# Microcontroller.net
KiCad netlist of a schematic drawn in Altium Designer
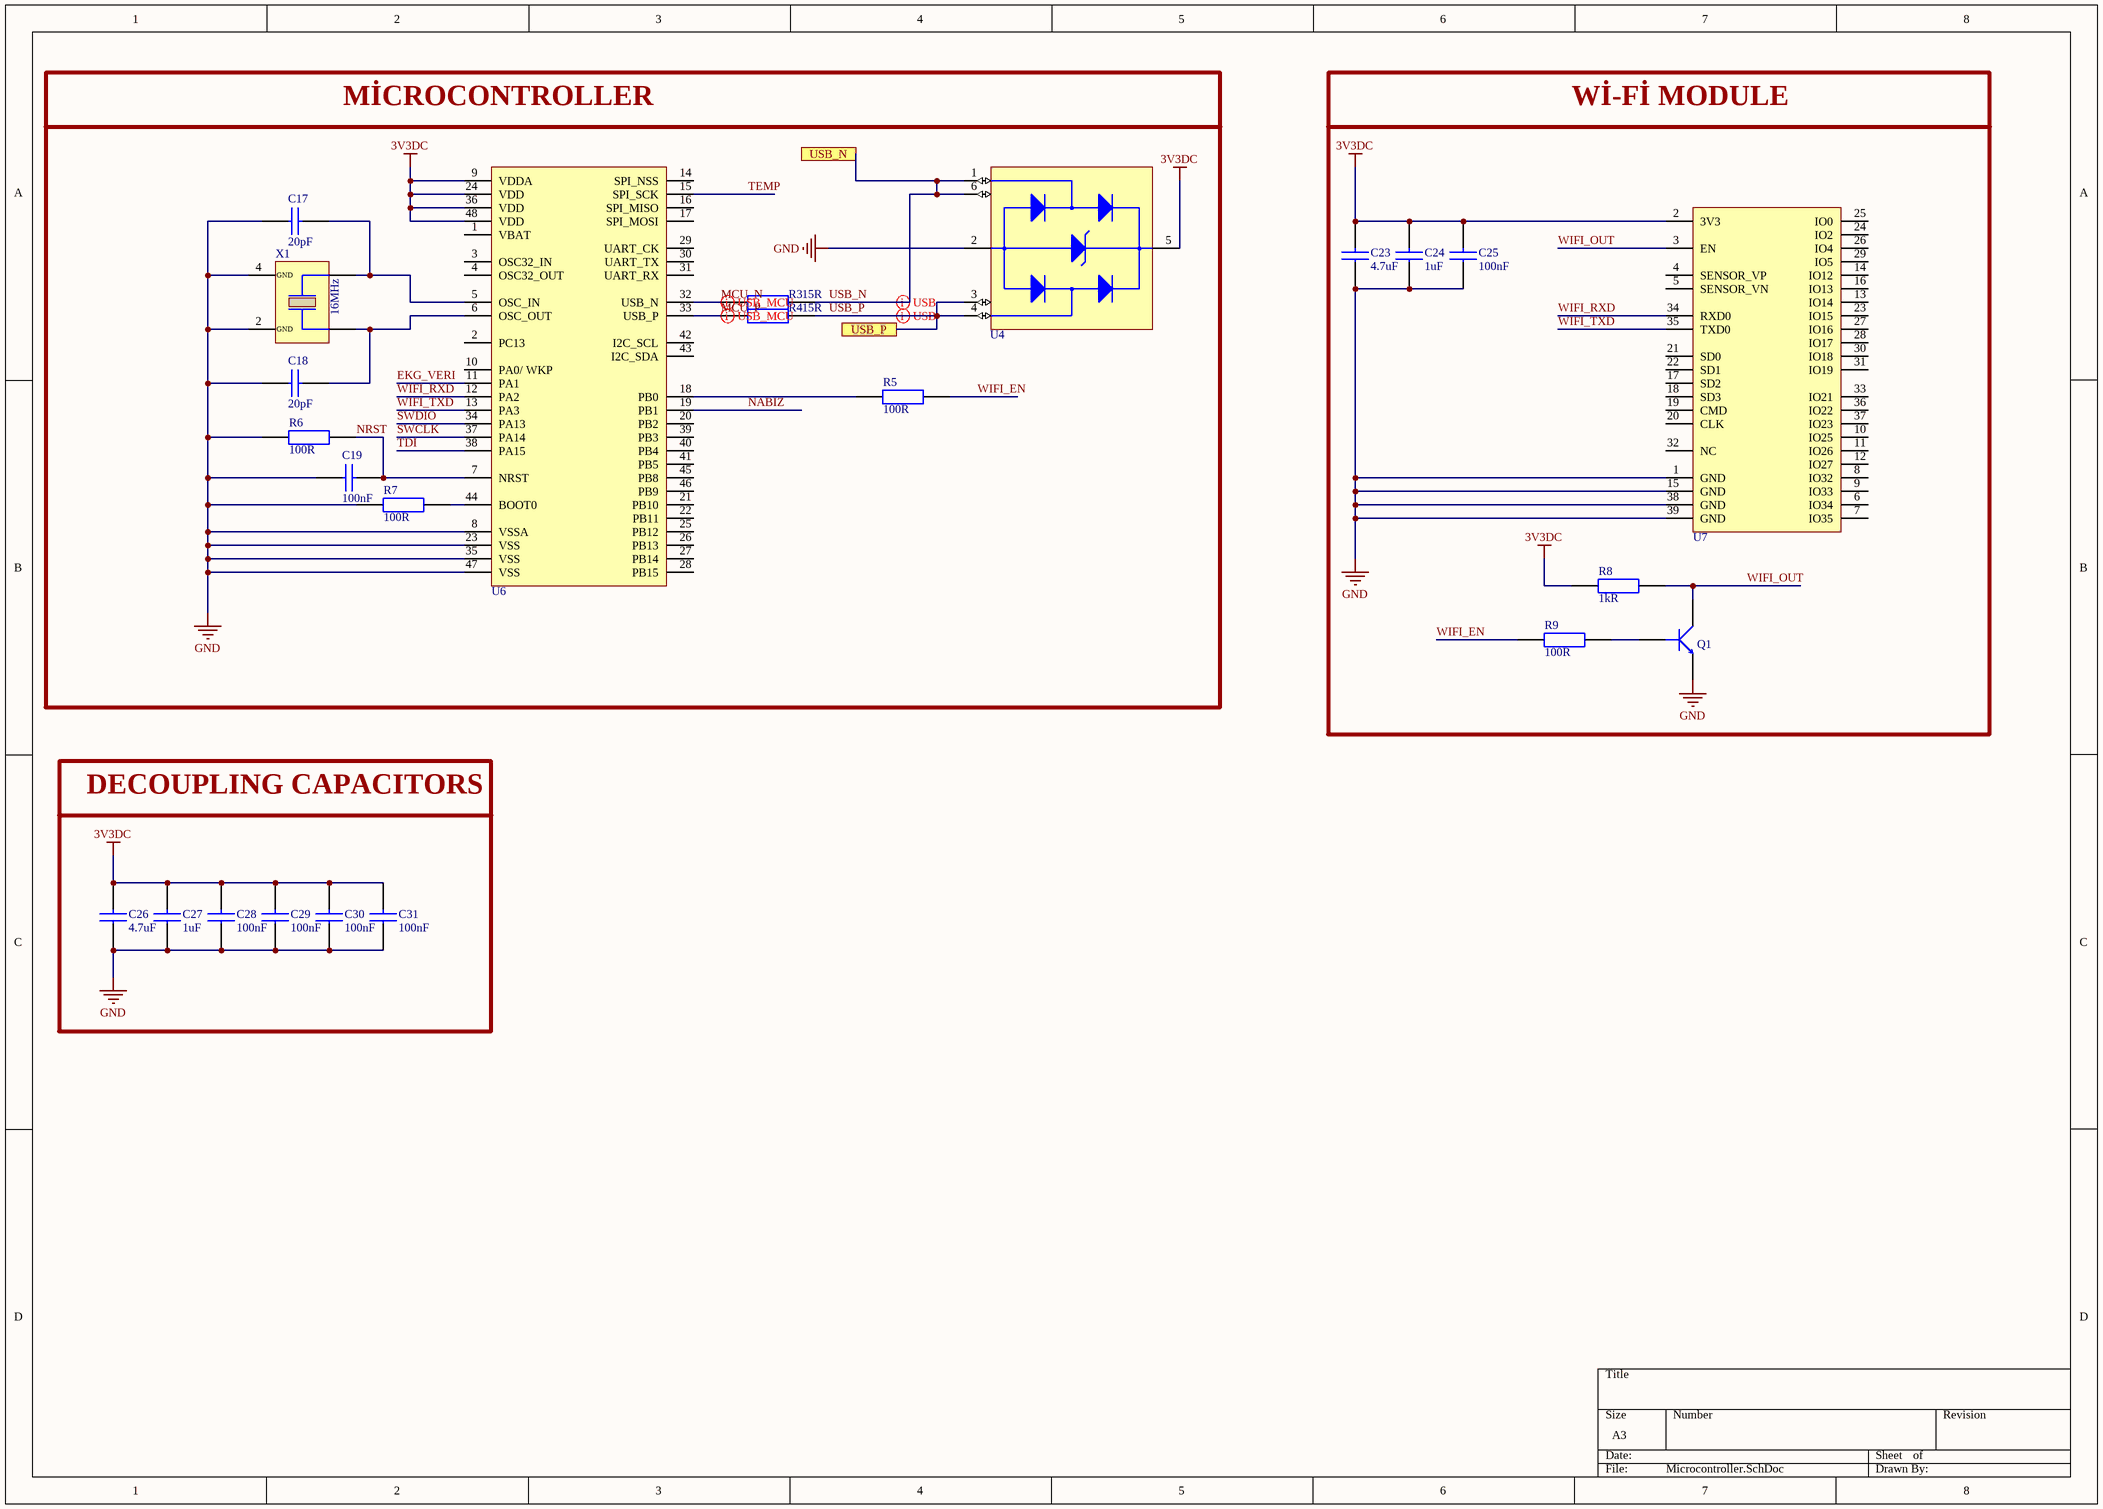
[diagram p0: Microcontroller.SchDoc]

(export (version "E")
  (design (tool "Eeschema 10.0.6"))
  (components
    (comp (ref "C17")
      (value "CL10C200JB8NNNC")
      (footprint "CAP_0603")
      (description "CAP CER 20pF %5 0603 SMD")
      (fields
        (field (name "MANUFACTURER") "Samsung")
        (field (name "TOLERANCE") "5%")
        (field (name "CAPACITANCE") "20pF")
        (field (name "DESIGNED BY") "TALAT")
      )
      (libsource (lib "Udemy_Library") (part "CAP CER 20pF 0603"))
    )
    (comp (ref "C18")
      (value "CL10C200JB8NNNC")
      (footprint "CAP_0603")
      (description "CAP CER 20pF %5 0603 SMD")
      (fields
        (field (name "MANUFACTURER") "Samsung")
        (field (name "TOLERANCE") "5%")
        (field (name "CAPACITANCE") "20pF")
        (field (name "DESIGNED BY") "TALAT")
      )
      (libsource (lib "Udemy_Library") (part "CAP CER 20pF 0603"))
    )
    (comp (ref "C19")
      (value "CL21B104KBCNNNC")
      (footprint "CAP_0805")
      (description "CAP CER 100nF %10 0805")
      (fields
        (field (name "MANUFACTURER") "Samsung")
        (field (name "TOLERANCE") "10%")
        (field (name "CAPACITANCE") "100nF")
        (field (name "DESIGNED BY") "TALAT")
      )
      (libsource (lib "Udemy_Library") (part "CAP CER 100nF 0805"))
    )
    (comp (ref "C23")
      (value "CL21A475KAQNNNE")
      (footprint "CAP_0805")
      (description "CAP CER 4.7uF %10 0805")
      (fields
        (field (name "MANUFACTURER") "Samsung")
        (field (name "TOLERANCE") "10%")
        (field (name "CAPACITANCE") "4.7uF")
        (field (name "DESIGNED BY") "TALAT")
      )
      (libsource (lib "Udemy_Library") (part "CAP CER 4.7uF 0805"))
    )
    (comp (ref "C24")
      (value "CL21B105KBFNNNE")
      (footprint "CAP_0805")
      (description "CAP CER 1uF %10 0805")
      (fields
        (field (name "MANUFACTURER") "Samsung")
        (field (name "TOLERANCE") "10%")
        (field (name "CAPACITANCE") "1uF")
        (field (name "DESIGNED BY") "TALAT")
      )
      (libsource (lib "Udemy_Library") (part "CAP CER 1uF 0805"))
    )
    (comp (ref "C25")
      (value "CL21B104KBCNNNC")
      (footprint "CAP_0805")
      (description "CAP CER 100nF %10 0805")
      (fields
        (field (name "MANUFACTURER") "Samsung")
        (field (name "TOLERANCE") "10%")
        (field (name "CAPACITANCE") "100nF")
        (field (name "DESIGNED BY") "TALAT")
      )
      (libsource (lib "Udemy_Library") (part "CAP CER 100nF 0805"))
    )
    (comp (ref "C26")
      (value "CL21A475KAQNNNE")
      (footprint "CAP_0805")
      (description "CAP CER 4.7uF %10 0805")
      (fields
        (field (name "MANUFACTURER") "Samsung")
        (field (name "TOLERANCE") "10%")
        (field (name "CAPACITANCE") "4.7uF")
        (field (name "DESIGNED BY") "TALAT")
      )
      (libsource (lib "Udemy_Library") (part "CAP CER 4.7uF 0805"))
    )
    (comp (ref "C27")
      (value "CL21B105KBFNNNE")
      (footprint "CAP_0805")
      (description "CAP CER 1uF %10 0805")
      (fields
        (field (name "MANUFACTURER") "Samsung")
        (field (name "TOLERANCE") "10%")
        (field (name "CAPACITANCE") "1uF")
        (field (name "DESIGNED BY") "TALAT")
      )
      (libsource (lib "Udemy_Library") (part "CAP CER 1uF 0805"))
    )
    (comp (ref "C28")
      (value "CL21B104KBCNNNC")
      (footprint "CAP_0805")
      (description "CAP CER 100nF %10 0805")
      (fields
        (field (name "MANUFACTURER") "Samsung")
        (field (name "TOLERANCE") "10%")
        (field (name "CAPACITANCE") "100nF")
        (field (name "DESIGNED BY") "TALAT")
      )
      (libsource (lib "Udemy_Library") (part "CAP CER 100nF 0805"))
    )
    (comp (ref "C29")
      (value "CL21B104KBCNNNC")
      (footprint "CAP_0805")
      (description "CAP CER 100nF %10 0805")
      (fields
        (field (name "MANUFACTURER") "Samsung")
        (field (name "TOLERANCE") "10%")
        (field (name "CAPACITANCE") "100nF")
        (field (name "DESIGNED BY") "TALAT")
      )
      (libsource (lib "Udemy_Library") (part "CAP CER 100nF 0805"))
    )
    (comp (ref "C30")
      (value "CL21B104KBCNNNC")
      (footprint "CAP_0805")
      (description "CAP CER 100nF %10 0805")
      (fields
        (field (name "MANUFACTURER") "Samsung")
        (field (name "TOLERANCE") "10%")
        (field (name "CAPACITANCE") "100nF")
        (field (name "DESIGNED BY") "TALAT")
      )
      (libsource (lib "Udemy_Library") (part "CAP CER 100nF 0805"))
    )
    (comp (ref "C31")
      (value "CL21B104KBCNNNC")
      (footprint "CAP_0805")
      (description "CAP CER 100nF %10 0805")
      (fields
        (field (name "MANUFACTURER") "Samsung")
        (field (name "TOLERANCE") "10%")
        (field (name "CAPACITANCE") "100nF")
        (field (name "DESIGNED BY") "TALAT")
      )
      (libsource (lib "Udemy_Library") (part "CAP CER 100nF 0805"))
    )
    (comp (ref "Q1")
      (value "MMBT3904-7-F")
      (footprint "SOT-23F")
      (description "Transistor General Purpose BJT NPN 40 Volt 0.2A Automotive 3-Pin SOT-23")
      (fields (field (name "MANUFACTURER") "Diodes Zetex") (field (name "DESIGNED BY") "TALAT"))
      (libsource (lib "Udemy_Library") (part "MMBT3904-7-F"))
    )
    (comp (ref "R3")
      (value "RC0603JR-0715RL")
      (footprint "RES_0603")
      (description "RES 15 %5 OHM 0603 SMD")
      (fields
        (field (name "MANUFACTURER") "Yageo")
        (field (name "TOLERANCE") "5%")
        (field (name "RESISTANCE") "15R")
        (field (name "DESIGNED BY") "TALAT")
      )
      (libsource (lib "Udemy_Library") (part "RES 15 OHM 0603"))
    )
    (comp (ref "R4")
      (value "RC0603JR-0715RL")
      (footprint "RES_0603")
      (description "RES 15 %5 OHM 0603 SMD")
      (fields
        (field (name "MANUFACTURER") "Yageo")
        (field (name "TOLERANCE") "5%")
        (field (name "RESISTANCE") "15R")
        (field (name "DESIGNED BY") "TALAT")
      )
      (libsource (lib "Udemy_Library") (part "RES 15 OHM 0603"))
    )
    (comp (ref "R5")
      (value "RC0603JR-07100RL")
      (footprint "RES_0603")
      (description "RES 100 %5 OHM 0603 SMD")
      (fields
        (field (name "MANUFACTURER") "Yageo")
        (field (name "TOLERANCE") "5%")
        (field (name "RESISTANCE") "100R")
        (field (name "DESIGNED BY") "TALAT")
      )
      (libsource (lib "Udemy_Library") (part "RES 100 OHM 0603"))
    )
    (comp (ref "R6")
      (value "RC0603JR-07100RL")
      (footprint "RES_0603")
      (description "RES 100 %5 OHM 0603 SMD")
      (fields
        (field (name "MANUFACTURER") "Yageo")
        (field (name "TOLERANCE") "5%")
        (field (name "RESISTANCE") "100R")
        (field (name "DESIGNED BY") "TALAT")
      )
      (libsource (lib "Udemy_Library") (part "RES 100 OHM 0603"))
    )
    (comp (ref "R7")
      (value "RC0603JR-07100RL")
      (footprint "RES_0603")
      (description "RES 100 %5 OHM 0603 SMD")
      (fields
        (field (name "MANUFACTURER") "Yageo")
        (field (name "TOLERANCE") "5%")
        (field (name "RESISTANCE") "100R")
        (field (name "DESIGNED BY") "TALAT")
      )
      (libsource (lib "Udemy_Library") (part "RES 100 OHM 0603"))
    )
    (comp (ref "R8")
      (value "RC0603FR-0710KL")
      (footprint "RES_0603")
      (description "RES 1K %1 OHM 0603 SMD")
      (fields
        (field (name "MANUFACTURER") "Yageo")
        (field (name "MANUFACTURER PART NUMBER") "RC0603JR-071KL")
        (field (name "RESISTANCE") "1kR")
        (field (name "DESIGNED BY") "TALAT")
      )
      (libsource (lib "Udemy_Library") (part "RES 1K OHM 0603"))
    )
    (comp (ref "R9")
      (value "RC0603JR-07100RL")
      (footprint "RES_0603")
      (description "RES 100 %5 OHM 0603 SMD")
      (fields
        (field (name "MANUFACTURER") "Yageo")
        (field (name "TOLERANCE") "5%")
        (field (name "RESISTANCE") "100R")
        (field (name "DESIGNED BY") "TALAT")
      )
      (libsource (lib "Udemy_Library") (part "RES 100 OHM 0603"))
    )
    (comp (ref "U4")
      (value "USBLC6-2SC6")
      (footprint "SOT23-6L")
      (description "TVS DIODE 5.25V 17V SOT23-6")
      (fields (field (name "MANUFACTURER") "STMicroelectronics") (field (name "DESIGNED BY") "TALAT"))
      (libsource (lib "Udemy_Library") (part "USB PROTECTION"))
    )
    (comp (ref "U6")
      (value "STM32F103C6T6A")
      (footprint "LQFP-48")
      (description "MCU 32-bit STM32F ARM Cortex M3 RISC 32KB Flash 2.5V/3.3V 48-Pin LQFP Tray")
      (fields (field (name "MANUFACTURER") "STMicroelectronics") (field (name "DESIGNED BY") "TALAT"))
      (libsource (lib "Udemy_Library") (part "STM32F103C6T6A"))
    )
    (comp (ref "U7")
      (value "ESP32-WROOM-32E (4MB)")
      (footprint "ESP32-32")
      (fields
        (field (name "MANUFACTURER") "Espressif Systems")
        (field (name "MANUFACTURER PART NUMBER") "ESP32-WROOM-32E(4MB)")
        (field (name "DESIGNED BY") "TALAT")
      )
      (libsource (lib "Udemy_Library") (part "ESP32-WROOM-32E (4MB)"))
    )
    (comp (ref "X1")
      (value "ECS-160-20-30B-TR")
      (footprint "ECS")
      (description "CRYSTAL 16.0000MHZ 20PF SMD")
      (fields
        (field (name "MANUFACTURER") "ECS International")
        (field (name "TOLERANCE") "50ppm")
        (field (name "FREQUENCY") "16MHz")
        (field (name "DESIGNED BY") "TALAT")
      )
      (libsource (lib "Udemy_Library") (part "CRYSTAL 16MHz"))
    )
  )
  (nets
    (net (code "1") (name "/EKG_VERI") (class "Default")
      (node (ref "U6") (pin "11") (pinfunction "PA1_11") (pintype "passive"))
    )
    (net (code "2") (name "/MCU_N") (class "Default")
      (node (ref "R3") (pin "1") (pinfunction "1_1") (pintype "passive"))
      (node (ref "U6") (pin "32") (pinfunction "USB_N_32") (pintype "passive"))
    )
    (net (code "3") (name "/MCU_P") (class "Default")
      (node (ref "R4") (pin "1") (pinfunction "1_1") (pintype "passive"))
      (node (ref "U6") (pin "33") (pinfunction "USB_P_33") (pintype "passive"))
    )
    (net (code "4") (name "/NABIZ") (class "Default")
      (node (ref "U6") (pin "19") (pinfunction "PB1_19") (pintype "passive"))
    )
    (net (code "5") (name "/NRST") (class "Default")
      (node (ref "C19") (pin "2") (pinfunction "2_2") (pintype "passive"))
      (node (ref "R6") (pin "2") (pinfunction "2_2") (pintype "passive"))
      (node (ref "U6") (pin "7") (pinfunction "NRST_7") (pintype "passive"))
    )
    (net (code "6") (name "/SWCLK") (class "Default")
      (node (ref "U6") (pin "37") (pinfunction "PA14_37") (pintype "passive"))
    )
    (net (code "7") (name "/SWDIO") (class "Default")
      (node (ref "U6") (pin "34") (pinfunction "PA13_34") (pintype "passive"))
    )
    (net (code "8") (name "/TDI") (class "Default")
      (node (ref "U6") (pin "38") (pinfunction "PA15_38") (pintype "passive"))
    )
    (net (code "9") (name "/TEMP") (class "Default")
      (node (ref "U6") (pin "15") (pinfunction "SPI_SCK_15") (pintype "passive"))
    )
    (net (code "10") (name "/USB_N") (class "Default")
      (node (ref "R3") (pin "2") (pinfunction "2_2") (pintype "passive"))
      (node (ref "U4") (pin "1") (pinfunction "I/O1_1") (pintype "bidirectional"))
      (node (ref "U4") (pin "6") (pinfunction "I/O1_6") (pintype "bidirectional"))
    )
    (net (code "11") (name "/USB_P") (class "Default")
      (node (ref "R4") (pin "2") (pinfunction "2_2") (pintype "passive"))
      (node (ref "U4") (pin "3") (pinfunction "I/O2_3") (pintype "bidirectional"))
      (node (ref "U4") (pin "4") (pinfunction "I/O2_4") (pintype "bidirectional"))
    )
    (net (code "12") (name "/WIFI_EN") (class "Default")
      (node (ref "R5") (pin "2") (pinfunction "2_2") (pintype "passive"))
      (node (ref "R9") (pin "1") (pinfunction "1_1") (pintype "passive"))
    )
    (net (code "13") (name "/WIFI_OUT") (class "Default")
      (node (ref "Q1") (pin "3") (pinfunction "C_3") (pintype "power_in"))
      (node (ref "R8") (pin "2") (pinfunction "2_2") (pintype "passive"))
      (node (ref "U7") (pin "3") (pinfunction "EN_3") (pintype "passive"))
    )
    (net (code "14") (name "/WIFI_RXD") (class "Default")
      (node (ref "U6") (pin "12") (pinfunction "PA2_12") (pintype "passive"))
      (node (ref "U7") (pin "34") (pinfunction "RXD0_34") (pintype "passive"))
    )
    (net (code "15") (name "/WIFI_TXD") (class "Default")
      (node (ref "U6") (pin "13") (pinfunction "PA3_13") (pintype "passive"))
      (node (ref "U7") (pin "35") (pinfunction "TXD0_35") (pintype "passive"))
    )
    (net (code "16") (name "3V3DC") (class "Default")
      (node (ref "C23") (pin "2") (pinfunction "2_2") (pintype "passive"))
      (node (ref "C24") (pin "2") (pinfunction "2_2") (pintype "passive"))
      (node (ref "C25") (pin "2") (pinfunction "2_2") (pintype "passive"))
      (node (ref "C26") (pin "2") (pinfunction "2_2") (pintype "passive"))
      (node (ref "C27") (pin "2") (pinfunction "2_2") (pintype "passive"))
      (node (ref "C28") (pin "2") (pinfunction "2_2") (pintype "passive"))
      (node (ref "C29") (pin "2") (pinfunction "2_2") (pintype "passive"))
      (node (ref "C30") (pin "2") (pinfunction "2_2") (pintype "passive"))
      (node (ref "C31") (pin "2") (pinfunction "2_2") (pintype "passive"))
      (node (ref "R8") (pin "1") (pinfunction "1_1") (pintype "passive"))
      (node (ref "U4") (pin "5") (pinfunction "VBUS_5") (pintype "power_in"))
      (node (ref "U6") (pin "24") (pinfunction "VDD_24") (pintype "passive"))
      (node (ref "U6") (pin "36") (pinfunction "VDD_36") (pintype "passive"))
      (node (ref "U6") (pin "48") (pinfunction "VDD_48") (pintype "passive"))
      (node (ref "U6") (pin "9") (pinfunction "VDDA_9") (pintype "passive"))
      (node (ref "U7") (pin "2") (pinfunction "3V3_2") (pintype "passive"))
    )
    (net (code "17") (name "GND") (class "Default")
      (node (ref "C17") (pin "1") (pinfunction "1_1") (pintype "passive"))
      (node (ref "C18") (pin "1") (pinfunction "1_1") (pintype "passive"))
      (node (ref "C19") (pin "1") (pinfunction "1_1") (pintype "passive"))
      (node (ref "C23") (pin "1") (pinfunction "1_1") (pintype "passive"))
      (node (ref "C24") (pin "1") (pinfunction "1_1") (pintype "passive"))
      (node (ref "C25") (pin "1") (pinfunction "1_1") (pintype "passive"))
      (node (ref "C26") (pin "1") (pinfunction "1_1") (pintype "passive"))
      (node (ref "C27") (pin "1") (pinfunction "1_1") (pintype "passive"))
      (node (ref "C28") (pin "1") (pinfunction "1_1") (pintype "passive"))
      (node (ref "C29") (pin "1") (pinfunction "1_1") (pintype "passive"))
      (node (ref "C30") (pin "1") (pinfunction "1_1") (pintype "passive"))
      (node (ref "C31") (pin "1") (pinfunction "1_1") (pintype "passive"))
      (node (ref "Q1") (pin "2") (pinfunction "E_2") (pintype "power_in"))
      (node (ref "R6") (pin "1") (pinfunction "1_1") (pintype "passive"))
      (node (ref "R7") (pin "1") (pinfunction "1_1") (pintype "passive"))
      (node (ref "U4") (pin "2") (pinfunction "GND_2") (pintype "power_in"))
      (node (ref "U6") (pin "23") (pinfunction "VSS_23") (pintype "passive"))
      (node (ref "U6") (pin "35") (pinfunction "VSS_35") (pintype "passive"))
      (node (ref "U6") (pin "47") (pinfunction "VSS_47") (pintype "passive"))
      (node (ref "U6") (pin "8") (pinfunction "VSSA_8") (pintype "passive"))
      (node (ref "U7") (pin "1") (pinfunction "GND_1") (pintype "passive"))
      (node (ref "U7") (pin "15") (pinfunction "GND_15") (pintype "passive"))
      (node (ref "U7") (pin "38") (pinfunction "GND_38") (pintype "passive"))
      (node (ref "U7") (pin "39") (pinfunction "GND_39") (pintype "passive"))
      (node (ref "X1") (pin "2") (pinfunction "GND_2") (pintype "passive"))
      (node (ref "X1") (pin "4") (pinfunction "GND_4") (pintype "passive"))
    )
    (net (code "18") (name "Net-(Q1-B)") (class "Default")
      (node (ref "Q1") (pin "1") (pinfunction "B_1") (pintype "power_in"))
      (node (ref "R9") (pin "2") (pinfunction "2_2") (pintype "passive"))
    )
    (net (code "19") (name "Net-(U6-BOOT0)") (class "Default")
      (node (ref "R7") (pin "2") (pinfunction "2_2") (pintype "passive"))
      (node (ref "U6") (pin "44") (pinfunction "BOOT0_44") (pintype "passive"))
    )
    (net (code "20") (name "Net-(U6-OSC_IN)") (class "Default")
      (node (ref "C17") (pin "2") (pinfunction "2_2") (pintype "passive"))
      (node (ref "U6") (pin "5") (pinfunction "OSC_IN_5") (pintype "passive"))
      (node (ref "X1") (pin "3") (pinfunction "3_3") (pintype "passive"))
    )
    (net (code "21") (name "Net-(U6-OSC_OUT)") (class "Default")
      (node (ref "C18") (pin "2") (pinfunction "2_2") (pintype "passive"))
      (node (ref "U6") (pin "6") (pinfunction "OSC_OUT_6") (pintype "passive"))
      (node (ref "X1") (pin "1") (pinfunction "1_1") (pintype "passive"))
    )
    (net (code "22") (name "Net-(U6-PB0)") (class "Default")
      (node (ref "R5") (pin "1") (pinfunction "1_1") (pintype "passive"))
      (node (ref "U6") (pin "18") (pinfunction "PB0_18") (pintype "passive"))
    )
    (net (code "23") (name "unconnected-(U6-I2C_SCL-Pad42)") (class "Default")
      (node (ref "U6") (pin "42") (pinfunction "I2C_SCL_42") (pintype "passive"))
    )
    (net (code "24") (name "unconnected-(U6-I2C_SDA-Pad43)") (class "Default")
      (node (ref "U6") (pin "43") (pinfunction "I2C_SDA_43") (pintype "passive"))
    )
    (net (code "25") (name "unconnected-(U6-OSC32_IN-Pad3)") (class "Default")
      (node (ref "U6") (pin "3") (pinfunction "OSC32_IN_3") (pintype "passive"))
    )
    (net (code "26") (name "unconnected-(U6-OSC32_OUT-Pad4)") (class "Default")
      (node (ref "U6") (pin "4") (pinfunction "OSC32_OUT_4") (pintype "passive"))
    )
    (net (code "27") (name "unconnected-(U6-PA0{slash}_WKP-Pad10)") (class "Default")
      (node (ref "U6") (pin "10") (pinfunction "PA0/_WKP_10") (pintype "passive"))
    )
    (net (code "28") (name "unconnected-(U6-PB2-Pad20)") (class "Default")
      (node (ref "U6") (pin "20") (pinfunction "PB2_20") (pintype "passive"))
    )
    (net (code "29") (name "unconnected-(U6-PB3-Pad39)") (class "Default")
      (node (ref "U6") (pin "39") (pinfunction "PB3_39") (pintype "passive"))
    )
    (net (code "30") (name "unconnected-(U6-PB4-Pad40)") (class "Default")
      (node (ref "U6") (pin "40") (pinfunction "PB4_40") (pintype "passive"))
    )
    (net (code "31") (name "unconnected-(U6-PB5-Pad41)") (class "Default")
      (node (ref "U6") (pin "41") (pinfunction "PB5_41") (pintype "passive"))
    )
    (net (code "32") (name "unconnected-(U6-PB8-Pad45)") (class "Default")
      (node (ref "U6") (pin "45") (pinfunction "PB8_45") (pintype "passive"))
    )
    (net (code "33") (name "unconnected-(U6-PB9-Pad46)") (class "Default")
      (node (ref "U6") (pin "46") (pinfunction "PB9_46") (pintype "passive"))
    )
    (net (code "34") (name "unconnected-(U6-PB10-Pad21)") (class "Default")
      (node (ref "U6") (pin "21") (pinfunction "PB10_21") (pintype "passive"))
    )
    (net (code "35") (name "unconnected-(U6-PB11-Pad22)") (class "Default")
      (node (ref "U6") (pin "22") (pinfunction "PB11_22") (pintype "passive"))
    )
    (net (code "36") (name "unconnected-(U6-PB12-Pad25)") (class "Default")
      (node (ref "U6") (pin "25") (pinfunction "PB12_25") (pintype "passive"))
    )
    (net (code "37") (name "unconnected-(U6-PB13-Pad26)") (class "Default")
      (node (ref "U6") (pin "26") (pinfunction "PB13_26") (pintype "passive"))
    )
    (net (code "38") (name "unconnected-(U6-PB14-Pad27)") (class "Default")
      (node (ref "U6") (pin "27") (pinfunction "PB14_27") (pintype "passive"))
    )
    (net (code "39") (name "unconnected-(U6-PB15-Pad28)") (class "Default")
      (node (ref "U6") (pin "28") (pinfunction "PB15_28") (pintype "passive"))
    )
    (net (code "40") (name "unconnected-(U6-PC13-Pad2)") (class "Default")
      (node (ref "U6") (pin "2") (pinfunction "PC13_2") (pintype "passive"))
    )
    (net (code "41") (name "unconnected-(U6-SPI_MISO-Pad16)") (class "Default")
      (node (ref "U6") (pin "16") (pinfunction "SPI_MISO_16") (pintype "passive"))
    )
    (net (code "42") (name "unconnected-(U6-SPI_MOSI-Pad17)") (class "Default")
      (node (ref "U6") (pin "17") (pinfunction "SPI_MOSI_17") (pintype "passive"))
    )
    (net (code "43") (name "unconnected-(U6-SPI_NSS-Pad14)") (class "Default")
      (node (ref "U6") (pin "14") (pinfunction "SPI_NSS_14") (pintype "passive"))
    )
    (net (code "44") (name "unconnected-(U6-UART_CK-Pad29)") (class "Default")
      (node (ref "U6") (pin "29") (pinfunction "UART_CK_29") (pintype "passive"))
    )
    (net (code "45") (name "unconnected-(U6-UART_RX-Pad31)") (class "Default")
      (node (ref "U6") (pin "31") (pinfunction "UART_RX_31") (pintype "passive"))
    )
    (net (code "46") (name "unconnected-(U6-UART_TX-Pad30)") (class "Default")
      (node (ref "U6") (pin "30") (pinfunction "UART_TX_30") (pintype "passive"))
    )
    (net (code "47") (name "unconnected-(U6-VBAT-Pad1)") (class "Default")
      (node (ref "U6") (pin "1") (pinfunction "VBAT_1") (pintype "passive"))
    )
    (net (code "48") (name "unconnected-(U7-CLK-Pad20)") (class "Default")
      (node (ref "U7") (pin "20") (pinfunction "CLK_20") (pintype "passive"))
    )
    (net (code "49") (name "unconnected-(U7-CMD-Pad19)") (class "Default")
      (node (ref "U7") (pin "19") (pinfunction "CMD_19") (pintype "passive"))
    )
    (net (code "50") (name "unconnected-(U7-IO0-Pad25)") (class "Default")
      (node (ref "U7") (pin "25") (pinfunction "IO0_25") (pintype "passive"))
    )
    (net (code "51") (name "unconnected-(U7-IO2-Pad24)") (class "Default")
      (node (ref "U7") (pin "24") (pinfunction "IO2_24") (pintype "passive"))
    )
    (net (code "52") (name "unconnected-(U7-IO4-Pad26)") (class "Default")
      (node (ref "U7") (pin "26") (pinfunction "IO4_26") (pintype "passive"))
    )
    (net (code "53") (name "unconnected-(U7-IO5-Pad29)") (class "Default")
      (node (ref "U7") (pin "29") (pinfunction "IO5_29") (pintype "passive"))
    )
    (net (code "54") (name "unconnected-(U7-IO12-Pad14)") (class "Default")
      (node (ref "U7") (pin "14") (pinfunction "IO12_14") (pintype "passive"))
    )
    (net (code "55") (name "unconnected-(U7-IO13-Pad16)") (class "Default")
      (node (ref "U7") (pin "16") (pinfunction "IO13_16") (pintype "passive"))
    )
    (net (code "56") (name "unconnected-(U7-IO14-Pad13)") (class "Default")
      (node (ref "U7") (pin "13") (pinfunction "IO14_13") (pintype "passive"))
    )
    (net (code "57") (name "unconnected-(U7-IO15-Pad23)") (class "Default")
      (node (ref "U7") (pin "23") (pinfunction "IO15_23") (pintype "passive"))
    )
    (net (code "58") (name "unconnected-(U7-IO16-Pad27)") (class "Default")
      (node (ref "U7") (pin "27") (pinfunction "IO16_27") (pintype "passive"))
    )
    (net (code "59") (name "unconnected-(U7-IO17-Pad28)") (class "Default")
      (node (ref "U7") (pin "28") (pinfunction "IO17_28") (pintype "passive"))
    )
    (net (code "60") (name "unconnected-(U7-IO18-Pad30)") (class "Default")
      (node (ref "U7") (pin "30") (pinfunction "IO18_30") (pintype "passive"))
    )
    (net (code "61") (name "unconnected-(U7-IO19-Pad31)") (class "Default")
      (node (ref "U7") (pin "31") (pinfunction "IO19_31") (pintype "passive"))
    )
    (net (code "62") (name "unconnected-(U7-IO21-Pad33)") (class "Default")
      (node (ref "U7") (pin "33") (pinfunction "IO21_33") (pintype "passive"))
    )
    (net (code "63") (name "unconnected-(U7-IO22-Pad36)") (class "Default")
      (node (ref "U7") (pin "36") (pinfunction "IO22_36") (pintype "passive"))
    )
    (net (code "64") (name "unconnected-(U7-IO23-Pad37)") (class "Default")
      (node (ref "U7") (pin "37") (pinfunction "IO23_37") (pintype "passive"))
    )
    (net (code "65") (name "unconnected-(U7-IO25-Pad10)") (class "Default")
      (node (ref "U7") (pin "10") (pinfunction "IO25_10") (pintype "passive"))
    )
    (net (code "66") (name "unconnected-(U7-IO26-Pad11)") (class "Default")
      (node (ref "U7") (pin "11") (pinfunction "IO26_11") (pintype "passive"))
    )
    (net (code "67") (name "unconnected-(U7-IO27-Pad12)") (class "Default")
      (node (ref "U7") (pin "12") (pinfunction "IO27_12") (pintype "passive"))
    )
    (net (code "68") (name "unconnected-(U7-IO32-Pad8)") (class "Default")
      (node (ref "U7") (pin "8") (pinfunction "IO32_8") (pintype "passive"))
    )
    (net (code "69") (name "unconnected-(U7-IO33-Pad9)") (class "Default")
      (node (ref "U7") (pin "9") (pinfunction "IO33_9") (pintype "passive"))
    )
    (net (code "70") (name "unconnected-(U7-IO34-Pad6)") (class "Default")
      (node (ref "U7") (pin "6") (pinfunction "IO34_6") (pintype "passive"))
    )
    (net (code "71") (name "unconnected-(U7-IO35-Pad7)") (class "Default")
      (node (ref "U7") (pin "7") (pinfunction "IO35_7") (pintype "passive"))
    )
    (net (code "72") (name "unconnected-(U7-NC-Pad32)") (class "Default")
      (node (ref "U7") (pin "32") (pinfunction "NC_32") (pintype "passive"))
    )
    (net (code "73") (name "unconnected-(U7-SD0-Pad21)") (class "Default")
      (node (ref "U7") (pin "21") (pinfunction "SD0_21") (pintype "passive"))
    )
    (net (code "74") (name "unconnected-(U7-SD1-Pad22)") (class "Default")
      (node (ref "U7") (pin "22") (pinfunction "SD1_22") (pintype "passive"))
    )
    (net (code "75") (name "unconnected-(U7-SD2-Pad17)") (class "Default")
      (node (ref "U7") (pin "17") (pinfunction "SD2_17") (pintype "passive"))
    )
    (net (code "76") (name "unconnected-(U7-SD3-Pad18)") (class "Default")
      (node (ref "U7") (pin "18") (pinfunction "SD3_18") (pintype "passive"))
    )
    (net (code "77") (name "unconnected-(U7-SENSOR_VN-Pad5)") (class "Default")
      (node (ref "U7") (pin "5") (pinfunction "SENSOR_VN_5") (pintype "passive"))
    )
    (net (code "78") (name "unconnected-(U7-SENSOR_VP-Pad4)") (class "Default")
      (node (ref "U7") (pin "4") (pinfunction "SENSOR_VP_4") (pintype "passive"))
    )
  )
)
